# Protect.net
KiCad netlist of a schematic drawn in Altium Designer
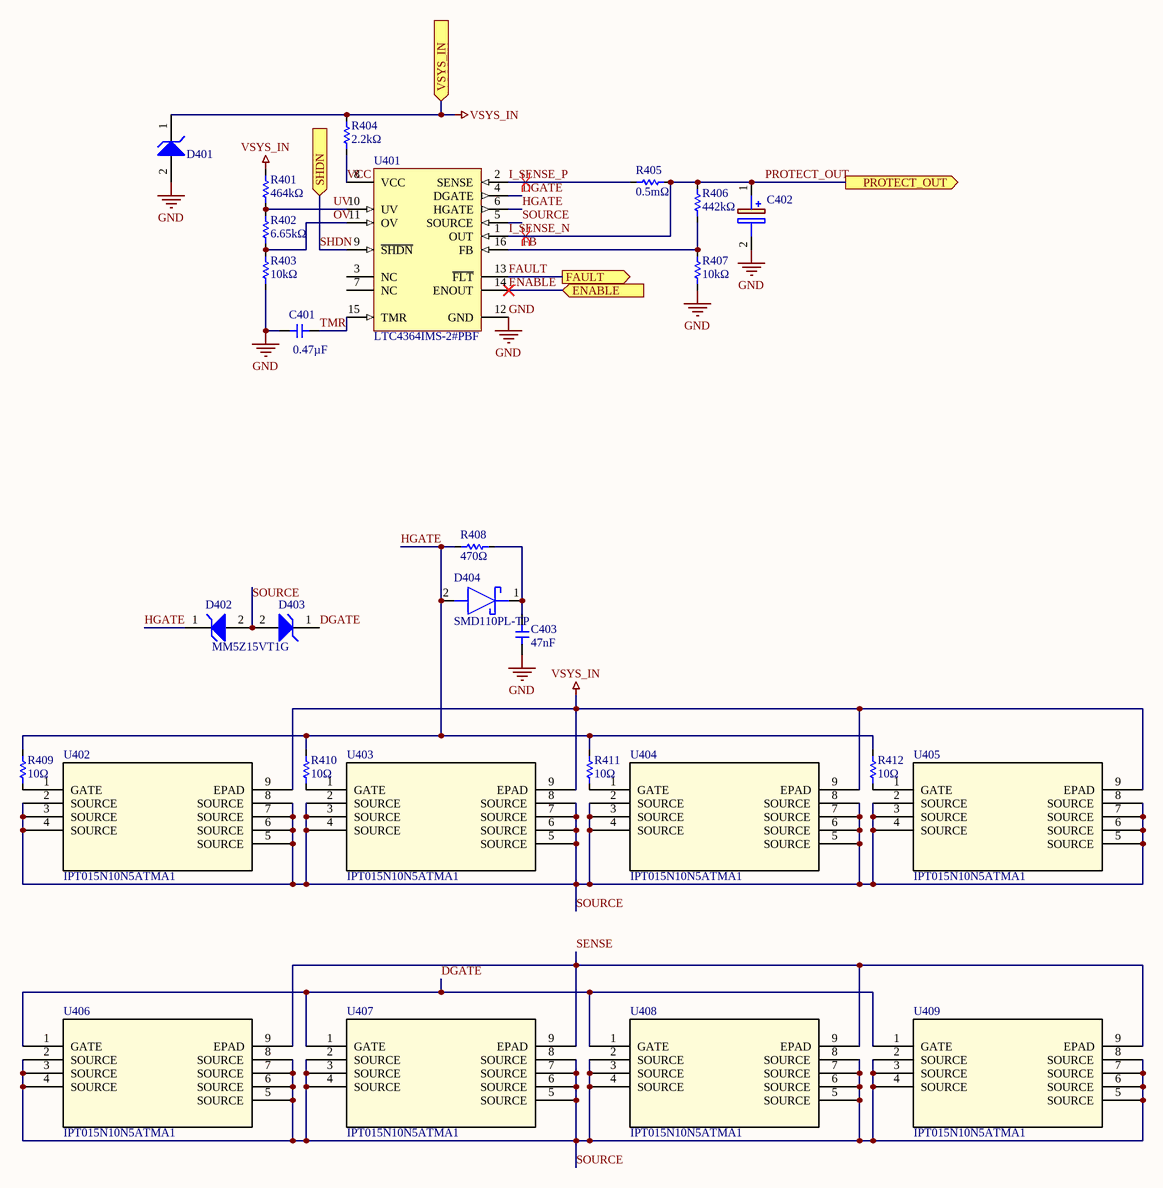
[diagram p0: Protect.SchDoc]

(export (version "E")
  (design (tool "Eeschema 10.0.6"))
  (components
    (comp (ref "C401")
      (value "non-polar_Capacitor")
      (footprint "1210")
      (description "SMD type ceramic capacitor")
      (fields
        (field (name "VOLTAGE") "50V")
        (field (name "CAPACITANCE") "0.47µF")
        (field (name "SOURCE") "robit_passive.SchLib")
      )
      (libsource (lib "robit circuit") (part "Capacitor"))
    )
    (comp (ref "C402")
      (value "B41858C9477M000")
      (footprint "SamacSys:CAPPRD750W90D1800H3700")
      (description "Capacitor Polarised")
      (fields (field (name "MOUSER PART NUMBER") "871-B41858C9477M"))
      (libsource (lib "*") (part "B41858C9477M000"))
    )
    (comp (ref "C403")
      (value "non-polar_Capacitor")
      (footprint "1210")
      (description "SMD type ceramic capacitor")
      (fields
        (field (name "VOLTAGE") "50V")
        (field (name "CAPACITANCE") "47nF")
        (field (name "SOURCE") "robit_passive.SchLib")
      )
      (libsource (lib "robit circuit") (part "Capacitor"))
    )
    (comp (ref "D401")
      (value "1SMB5945BT3G")
      (footprint "ONSC-SMB-2-403A-03_H_V")
      (description "3 W Zener Voltage Regulator, 2-Pin SMB, Pb-Free, Tape and Reel")
      (fields (field (name "MANUFACTURER") "On Semiconductor"))
      (libsource (lib "Altium Content Vault") (part "ONSC-K1A2-2"))
    )
    (comp (ref "D402")
      (value "MM5Z15VT1G")
      (footprint "ONSC-SOD-523-2-502-01_V")
      (description "Zener Voltage Regulator, 500 mW, 2-Pin SOD-523, Pb-Free, Tape and Reel")
      (fields (field (name "MANUFACTURER") "On Semiconductor"))
      (libsource (lib "Altium Content Vault") (part "ONSC-K1A2-2"))
    )
    (comp (ref "D403")
      (value "MM5Z15VT1G")
      (footprint "ONSC-SOD-523-2-502-01_V")
      (description "Zener Voltage Regulator, 500 mW, 2-Pin SOD-523, Pb-Free, Tape and Reel")
      (fields (field (name "MANUFACTURER") "On Semiconductor"))
      (libsource (lib "Altium Content Vault") (part "ONSC-K1A2-2"))
    )
    (comp (ref "D404")
      (value "SMD110PL-TP")
      (footprint "SamacSys:SODFL3616X135N")
      (description "Schottky Diode")
      (fields (field (name "MOUSER PART NUMBER") "833-SMD110PL-TP"))
      (libsource (lib "*") (part "SMD110PL-TP"))
    )
    (comp (ref "R401") (value "464kΩ") (footprint "SMD_0603") (libsource (lib "Resistor") (part "Resistor")))
    (comp (ref "R402") (value "6.65kΩ") (footprint "SMD_0603") (libsource (lib "Resistor") (part "Resistor")))
    (comp (ref "R403") (value "10kΩ") (footprint "SMD_0603") (libsource (lib "Resistor") (part "Resistor")))
    (comp (ref "R404") (value "2.2kΩ") (footprint "SMD_2512") (libsource (lib "Resistor") (part "Resistor")))
    (comp (ref "R405") (value "0.5mΩ") (footprint "SMD_2512") (libsource (lib "Resistor") (part "Resistor")))
    (comp (ref "R406") (value "442kΩ") (footprint "SMD_0603") (libsource (lib "Resistor") (part "Resistor")))
    (comp (ref "R407") (value "10kΩ") (footprint "SMD_0603") (libsource (lib "Resistor") (part "Resistor")))
    (comp (ref "R408")
      (value "470Ω")
      (footprint "SMD_0603")
      (description "0.1W, 0603")
      (libsource (lib "Resistor") (part "Resistor"))
    )
    (comp (ref "R409") (value "10Ω") (footprint "SMD_0603") (libsource (lib "Resistor") (part "Resistor")))
    (comp (ref "R410") (value "10Ω") (footprint "SMD_0603") (libsource (lib "Resistor") (part "Resistor")))
    (comp (ref "R411") (value "10Ω") (footprint "SMD_0603") (libsource (lib "Resistor") (part "Resistor")))
    (comp (ref "R412") (value "10Ω") (footprint "SMD_0603") (libsource (lib "Resistor") (part "Resistor")))
    (comp (ref "U401")
      (value "LTC4364IMS-2#PBF")
      (footprint "LT-MS-16_M")
      (description "Surge Stopper with Ideal Diode, 4 to 80 V Vin, 16-pin SOP (MS-16), -40 to 85 degC, Pb-Free")
      (fields (field (name "MANUFACTURER") "Linear Technology"))
      (libsource (lib "Altium Content Vault") (part "LT-LTC4364-S-16"))
    )
    (comp (ref "U402")
      (value "IPT015N10N5ATMA1")
      (footprint "PG-HSOF-8-1_INF")
      (fields (field (name "COPYRIGHT") "Copyright (C) 2025 Ultra Librarian. All rights reserved."))
      (libsource (lib "IPT015N10N5ATMA1") (part "IPT015N10N5ATMA1"))
    )
    (comp (ref "U403")
      (value "IPT015N10N5ATMA1")
      (footprint "PG-HSOF-8-1_INF")
      (fields (field (name "COPYRIGHT") "Copyright (C) 2025 Ultra Librarian. All rights reserved."))
      (libsource (lib "IPT015N10N5ATMA1") (part "IPT015N10N5ATMA1"))
    )
    (comp (ref "U404")
      (value "IPT015N10N5ATMA1")
      (footprint "PG-HSOF-8-1_INF")
      (fields (field (name "COPYRIGHT") "Copyright (C) 2025 Ultra Librarian. All rights reserved."))
      (libsource (lib "IPT015N10N5ATMA1") (part "IPT015N10N5ATMA1"))
    )
    (comp (ref "U405")
      (value "IPT015N10N5ATMA1")
      (footprint "PG-HSOF-8-1_INF")
      (fields (field (name "COPYRIGHT") "Copyright (C) 2025 Ultra Librarian. All rights reserved."))
      (libsource (lib "IPT015N10N5ATMA1") (part "IPT015N10N5ATMA1"))
    )
    (comp (ref "U406")
      (value "IPT015N10N5ATMA1")
      (footprint "PG-HSOF-8-1_INF")
      (fields (field (name "COPYRIGHT") "Copyright (C) 2025 Ultra Librarian. All rights reserved."))
      (libsource (lib "IPT015N10N5ATMA1") (part "IPT015N10N5ATMA1"))
    )
    (comp (ref "U407")
      (value "IPT015N10N5ATMA1")
      (footprint "PG-HSOF-8-1_INF")
      (fields (field (name "COPYRIGHT") "Copyright (C) 2025 Ultra Librarian. All rights reserved."))
      (libsource (lib "IPT015N10N5ATMA1") (part "IPT015N10N5ATMA1"))
    )
    (comp (ref "U408")
      (value "IPT015N10N5ATMA1")
      (footprint "PG-HSOF-8-1_INF")
      (fields (field (name "COPYRIGHT") "Copyright (C) 2025 Ultra Librarian. All rights reserved."))
      (libsource (lib "IPT015N10N5ATMA1") (part "IPT015N10N5ATMA1"))
    )
    (comp (ref "U409")
      (value "IPT015N10N5ATMA1")
      (footprint "PG-HSOF-8-1_INF")
      (fields (field (name "COPYRIGHT") "Copyright (C) 2025 Ultra Librarian. All rights reserved."))
      (libsource (lib "IPT015N10N5ATMA1") (part "IPT015N10N5ATMA1"))
    )
  )
  (nets
    (net (code "1") (name "/DGATE") (class "Default")
      (node (ref "D403") (pin "1") (pinfunction "K_1") (pintype "passive"))
      (node (ref "U401") (pin "4") (pinfunction "DGATE_4") (pintype "output"))
      (node (ref "U406") (pin "1") (pinfunction "GATE_1") (pintype "passive"))
      (node (ref "U407") (pin "1") (pinfunction "GATE_1") (pintype "passive"))
      (node (ref "U408") (pin "1") (pinfunction "GATE_1") (pintype "passive"))
      (node (ref "U409") (pin "1") (pinfunction "GATE_1") (pintype "passive"))
    )
    (net (code "2") (name "/ENABLE") (class "Default")
      (node (ref "U401") (pin "14") (pinfunction "ENOUT_14") (pintype "tri_state+no_connect"))
    )
    (net (code "3") (name "/FAULT") (class "Default")
      (node (ref "U401") (pin "13") (pinfunction "~{FLT}_13") (pintype "tri_state"))
    )
    (net (code "4") (name "/FB") (class "Default")
      (node (ref "R406") (pin "2") (pinfunction "2_2") (pintype "passive"))
      (node (ref "R407") (pin "1") (pinfunction "1_1") (pintype "passive"))
      (node (ref "U401") (pin "16") (pinfunction "FB_16") (pintype "input"))
    )
    (net (code "5") (name "/HGATE") (class "Default")
      (node (ref "D402") (pin "1") (pinfunction "K_1") (pintype "passive"))
      (node (ref "D404") (pin "2") (pinfunction "A_2") (pintype "passive"))
      (node (ref "R408") (pin "1") (pinfunction "1_1") (pintype "passive"))
      (node (ref "R409") (pin "1") (pinfunction "1_1") (pintype "passive"))
      (node (ref "R410") (pin "1") (pinfunction "1_1") (pintype "passive"))
      (node (ref "R411") (pin "1") (pinfunction "1_1") (pintype "passive"))
      (node (ref "R412") (pin "1") (pinfunction "1_1") (pintype "passive"))
      (node (ref "U401") (pin "6") (pinfunction "HGATE_6") (pintype "output"))
    )
    (net (code "6") (name "/I_SENSE_N") (class "Default")
      (node (ref "C402") (pin "1") (pinfunction "+_1") (pintype "passive"))
      (node (ref "R405") (pin "2") (pinfunction "2_2") (pintype "passive"))
      (node (ref "R406") (pin "1") (pinfunction "1_1") (pintype "passive"))
      (node (ref "U401") (pin "1") (pinfunction "OUT_1") (pintype "input"))
    )
    (net (code "7") (name "/I_SENSE_P") (class "Default")
      (node (ref "R405") (pin "1") (pinfunction "1_1") (pintype "passive"))
      (node (ref "U401") (pin "2") (pinfunction "SENSE_2") (pintype "input"))
    )
    (net (code "8") (name "/OV") (class "Default")
      (node (ref "R402") (pin "2") (pinfunction "2_2") (pintype "passive"))
      (node (ref "R403") (pin "1") (pinfunction "1_1") (pintype "passive"))
      (node (ref "U401") (pin "11") (pinfunction "OV_11") (pintype "input"))
    )
    (net (code "9") (name "/SENSE") (class "Default")
      (node (ref "U406") (pin "9") (pinfunction "EPAD_9") (pintype "passive"))
      (node (ref "U407") (pin "9") (pinfunction "EPAD_9") (pintype "passive"))
      (node (ref "U408") (pin "9") (pinfunction "EPAD_9") (pintype "passive"))
      (node (ref "U409") (pin "9") (pinfunction "EPAD_9") (pintype "passive"))
    )
    (net (code "10") (name "/SHDN") (class "Default")
      (node (ref "U401") (pin "9") (pinfunction "~{SHDN}_9") (pintype "input"))
    )
    (net (code "11") (name "/SOURCE") (class "Default")
      (node (ref "D402") (pin "2") (pinfunction "A_2") (pintype "passive"))
      (node (ref "D403") (pin "2") (pinfunction "A_2") (pintype "passive"))
      (node (ref "U401") (pin "5") (pinfunction "SOURCE_5") (pintype "input"))
      (node (ref "U402") (pin "2") (pinfunction "SOURCE_2") (pintype "passive"))
      (node (ref "U402") (pin "3") (pinfunction "SOURCE_3") (pintype "passive"))
      (node (ref "U402") (pin "4") (pinfunction "SOURCE_4") (pintype "passive"))
      (node (ref "U402") (pin "5") (pinfunction "SOURCE_5") (pintype "passive"))
      (node (ref "U402") (pin "6") (pinfunction "SOURCE_6") (pintype "passive"))
      (node (ref "U402") (pin "7") (pinfunction "SOURCE_7") (pintype "passive"))
      (node (ref "U402") (pin "8") (pinfunction "SOURCE_8") (pintype "passive"))
      (node (ref "U403") (pin "2") (pinfunction "SOURCE_2") (pintype "passive"))
      (node (ref "U403") (pin "3") (pinfunction "SOURCE_3") (pintype "passive"))
      (node (ref "U403") (pin "4") (pinfunction "SOURCE_4") (pintype "passive"))
      (node (ref "U403") (pin "5") (pinfunction "SOURCE_5") (pintype "passive"))
      (node (ref "U403") (pin "6") (pinfunction "SOURCE_6") (pintype "passive"))
      (node (ref "U403") (pin "7") (pinfunction "SOURCE_7") (pintype "passive"))
      (node (ref "U403") (pin "8") (pinfunction "SOURCE_8") (pintype "passive"))
      (node (ref "U404") (pin "2") (pinfunction "SOURCE_2") (pintype "passive"))
      (node (ref "U404") (pin "3") (pinfunction "SOURCE_3") (pintype "passive"))
      (node (ref "U404") (pin "4") (pinfunction "SOURCE_4") (pintype "passive"))
      (node (ref "U404") (pin "5") (pinfunction "SOURCE_5") (pintype "passive"))
      (node (ref "U404") (pin "6") (pinfunction "SOURCE_6") (pintype "passive"))
      (node (ref "U404") (pin "7") (pinfunction "SOURCE_7") (pintype "passive"))
      (node (ref "U404") (pin "8") (pinfunction "SOURCE_8") (pintype "passive"))
      (node (ref "U405") (pin "2") (pinfunction "SOURCE_2") (pintype "passive"))
      (node (ref "U405") (pin "3") (pinfunction "SOURCE_3") (pintype "passive"))
      (node (ref "U405") (pin "4") (pinfunction "SOURCE_4") (pintype "passive"))
      (node (ref "U405") (pin "5") (pinfunction "SOURCE_5") (pintype "passive"))
      (node (ref "U405") (pin "6") (pinfunction "SOURCE_6") (pintype "passive"))
      (node (ref "U405") (pin "7") (pinfunction "SOURCE_7") (pintype "passive"))
      (node (ref "U405") (pin "8") (pinfunction "SOURCE_8") (pintype "passive"))
      (node (ref "U406") (pin "2") (pinfunction "SOURCE_2") (pintype "passive"))
      (node (ref "U406") (pin "3") (pinfunction "SOURCE_3") (pintype "passive"))
      (node (ref "U406") (pin "4") (pinfunction "SOURCE_4") (pintype "passive"))
      (node (ref "U406") (pin "5") (pinfunction "SOURCE_5") (pintype "passive"))
      (node (ref "U406") (pin "6") (pinfunction "SOURCE_6") (pintype "passive"))
      (node (ref "U406") (pin "7") (pinfunction "SOURCE_7") (pintype "passive"))
      (node (ref "U406") (pin "8") (pinfunction "SOURCE_8") (pintype "passive"))
      (node (ref "U407") (pin "2") (pinfunction "SOURCE_2") (pintype "passive"))
      (node (ref "U407") (pin "3") (pinfunction "SOURCE_3") (pintype "passive"))
      (node (ref "U407") (pin "4") (pinfunction "SOURCE_4") (pintype "passive"))
      (node (ref "U407") (pin "5") (pinfunction "SOURCE_5") (pintype "passive"))
      (node (ref "U407") (pin "6") (pinfunction "SOURCE_6") (pintype "passive"))
      (node (ref "U407") (pin "7") (pinfunction "SOURCE_7") (pintype "passive"))
      (node (ref "U407") (pin "8") (pinfunction "SOURCE_8") (pintype "passive"))
      (node (ref "U408") (pin "2") (pinfunction "SOURCE_2") (pintype "passive"))
      (node (ref "U408") (pin "3") (pinfunction "SOURCE_3") (pintype "passive"))
      (node (ref "U408") (pin "4") (pinfunction "SOURCE_4") (pintype "passive"))
      (node (ref "U408") (pin "5") (pinfunction "SOURCE_5") (pintype "passive"))
      (node (ref "U408") (pin "6") (pinfunction "SOURCE_6") (pintype "passive"))
      (node (ref "U408") (pin "7") (pinfunction "SOURCE_7") (pintype "passive"))
      (node (ref "U408") (pin "8") (pinfunction "SOURCE_8") (pintype "passive"))
      (node (ref "U409") (pin "2") (pinfunction "SOURCE_2") (pintype "passive"))
      (node (ref "U409") (pin "3") (pinfunction "SOURCE_3") (pintype "passive"))
      (node (ref "U409") (pin "4") (pinfunction "SOURCE_4") (pintype "passive"))
      (node (ref "U409") (pin "5") (pinfunction "SOURCE_5") (pintype "passive"))
      (node (ref "U409") (pin "6") (pinfunction "SOURCE_6") (pintype "passive"))
      (node (ref "U409") (pin "7") (pinfunction "SOURCE_7") (pintype "passive"))
      (node (ref "U409") (pin "8") (pinfunction "SOURCE_8") (pintype "passive"))
    )
    (net (code "12") (name "/TMR") (class "Default")
      (node (ref "C401") (pin "2") (pinfunction "2_2") (pintype "passive"))
      (node (ref "U401") (pin "15") (pinfunction "TMR_15") (pintype "input"))
    )
    (net (code "13") (name "/UV") (class "Default")
      (node (ref "R401") (pin "2") (pinfunction "2_2") (pintype "passive"))
      (node (ref "R402") (pin "1") (pinfunction "1_1") (pintype "passive"))
      (node (ref "U401") (pin "10") (pinfunction "UV_10") (pintype "input"))
    )
    (net (code "14") (name "/VCC") (class "Default")
      (node (ref "R404") (pin "2") (pinfunction "2_2") (pintype "passive"))
      (node (ref "U401") (pin "8") (pinfunction "VCC_8") (pintype "power_in"))
    )
    (net (code "15") (name "GND") (class "Default")
      (node (ref "C401") (pin "1") (pinfunction "1_1") (pintype "passive"))
      (node (ref "C402") (pin "2") (pinfunction "-_2") (pintype "passive"))
      (node (ref "C403") (pin "1") (pinfunction "1_1") (pintype "passive"))
      (node (ref "D401") (pin "2") (pinfunction "A_2") (pintype "passive"))
      (node (ref "R403") (pin "2") (pinfunction "2_2") (pintype "passive"))
      (node (ref "R407") (pin "2") (pinfunction "2_2") (pintype "passive"))
      (node (ref "U401") (pin "12") (pinfunction "GND_12") (pintype "power_in"))
    )
    (net (code "16") (name "Net-(D404-K)") (class "Default")
      (node (ref "C403") (pin "2") (pinfunction "2_2") (pintype "passive"))
      (node (ref "D404") (pin "1") (pinfunction "K_1") (pintype "passive"))
      (node (ref "R408") (pin "2") (pinfunction "2_2") (pintype "passive"))
    )
    (net (code "17") (name "Net-(U402-GATE)") (class "Default")
      (node (ref "R409") (pin "2") (pinfunction "2_2") (pintype "passive"))
      (node (ref "U402") (pin "1") (pinfunction "GATE_1") (pintype "passive"))
    )
    (net (code "18") (name "Net-(U403-GATE)") (class "Default")
      (node (ref "R410") (pin "2") (pinfunction "2_2") (pintype "passive"))
      (node (ref "U403") (pin "1") (pinfunction "GATE_1") (pintype "passive"))
    )
    (net (code "19") (name "Net-(U404-GATE)") (class "Default")
      (node (ref "R411") (pin "2") (pinfunction "2_2") (pintype "passive"))
      (node (ref "U404") (pin "1") (pinfunction "GATE_1") (pintype "passive"))
    )
    (net (code "20") (name "Net-(U405-GATE)") (class "Default")
      (node (ref "R412") (pin "2") (pinfunction "2_2") (pintype "passive"))
      (node (ref "U405") (pin "1") (pinfunction "GATE_1") (pintype "passive"))
    )
    (net (code "21") (name "VSYS_IN") (class "Default")
      (node (ref "D401") (pin "1") (pinfunction "K_1") (pintype "passive"))
      (node (ref "R401") (pin "1") (pinfunction "1_1") (pintype "passive"))
      (node (ref "R404") (pin "1") (pinfunction "1_1") (pintype "passive"))
      (node (ref "U402") (pin "9") (pinfunction "EPAD_9") (pintype "passive"))
      (node (ref "U403") (pin "9") (pinfunction "EPAD_9") (pintype "passive"))
      (node (ref "U404") (pin "9") (pinfunction "EPAD_9") (pintype "passive"))
      (node (ref "U405") (pin "9") (pinfunction "EPAD_9") (pintype "passive"))
    )
    (net (code "22") (name "unconnected-(U401-NC-Pad3)") (class "Default")
      (node (ref "U401") (pin "3") (pinfunction "NC_3") (pintype "passive"))
    )
    (net (code "23") (name "unconnected-(U401-NC-Pad7)") (class "Default")
      (node (ref "U401") (pin "7") (pinfunction "NC_7") (pintype "passive"))
    )
  )
)
